# schematic_easyeda.net
KiCad netlist of a schematic drawn in EasyEDA
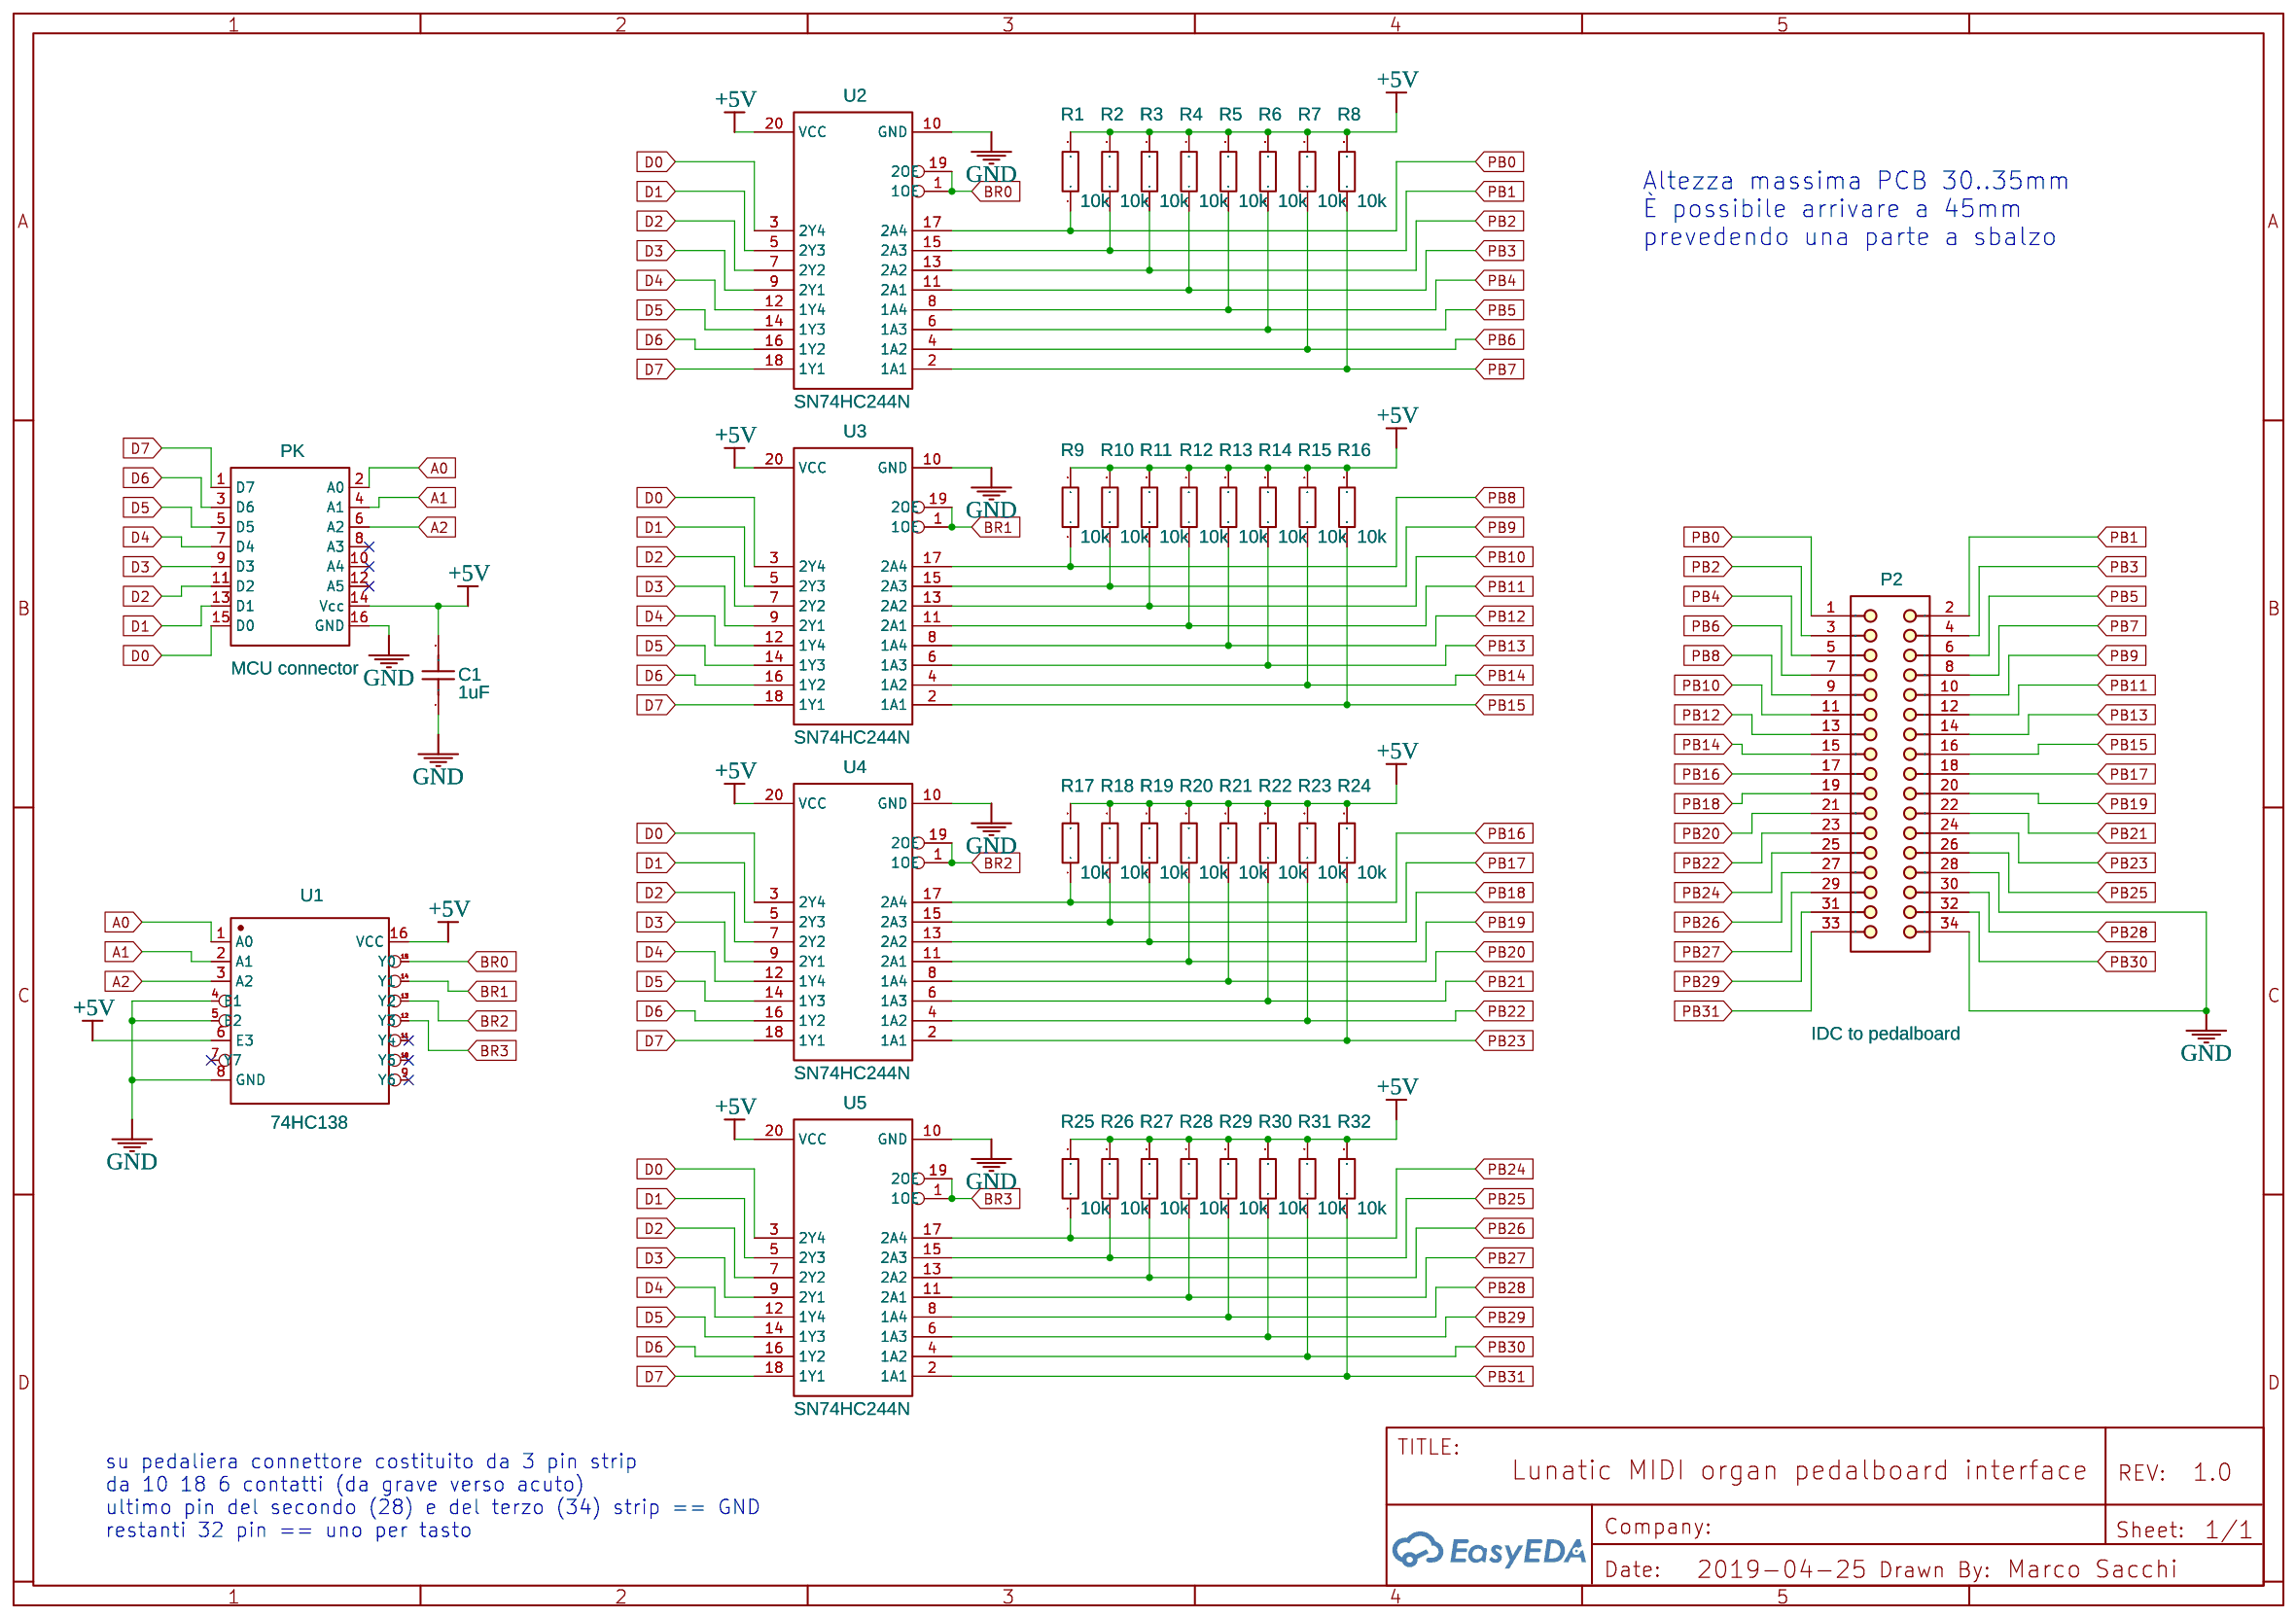
[diagram p0: schematic sheet]

(export (version "E")
  (design (tool "Eeschema 10.0.6"))
  (components
    (comp (ref "C1")
      (value "1uF")
      (fields (field (name "BOM_Manufacturer Part") "?"))
      (libsource (lib "") (part "Cap_RAD-0.1_US"))
    )
    (comp (ref "P2")
      (value "IDC to pedalboard")
      (fields
        (field (name "BOM_Manufacturer Part") "AWHW 34G-0202-T")
        (field (name "BOM_Supplier Part") "674-1243")
      )
      (libsource (lib "") (part "Unknown_950_385"))
    )
    (comp (ref "PK")
      (value "MCU connector")
      (fields (field (name "BOM_Manufacturer Part") "GEM"))
      (libsource (lib "") (part "Unknown_130_270"))
    )
    (comp (ref "R1")
      (value "10k")
      (fields (field (name "BOM_Manufacturer Part") "?"))
      (libsource (lib "") (part "Res_AXIAL-0.3(1/8W)_EU"))
    )
    (comp (ref "R2")
      (value "10k")
      (fields (field (name "BOM_Manufacturer Part") "?"))
      (libsource (lib "") (part "Res_AXIAL-0.3(1/8W)_EU"))
    )
    (comp (ref "R3")
      (value "10k")
      (fields (field (name "BOM_Manufacturer Part") "?"))
      (libsource (lib "") (part "Res_AXIAL-0.3(1/8W)_EU"))
    )
    (comp (ref "R4")
      (value "10k")
      (fields (field (name "BOM_Manufacturer Part") "?"))
      (libsource (lib "") (part "Res_AXIAL-0.3(1/8W)_EU"))
    )
    (comp (ref "R5")
      (value "10k")
      (fields (field (name "BOM_Manufacturer Part") "?"))
      (libsource (lib "") (part "Res_AXIAL-0.3(1/8W)_EU"))
    )
    (comp (ref "R6")
      (value "10k")
      (fields (field (name "BOM_Manufacturer Part") "?"))
      (libsource (lib "") (part "Res_AXIAL-0.3(1/8W)_EU"))
    )
    (comp (ref "R7")
      (value "10k")
      (fields (field (name "BOM_Manufacturer Part") "?"))
      (libsource (lib "") (part "Res_AXIAL-0.3(1/8W)_EU"))
    )
    (comp (ref "R8")
      (value "10k")
      (fields (field (name "BOM_Manufacturer Part") "?"))
      (libsource (lib "") (part "Res_AXIAL-0.3(1/8W)_EU"))
    )
    (comp (ref "R9")
      (value "10k")
      (fields (field (name "BOM_Manufacturer Part") "?"))
      (libsource (lib "") (part "Res_AXIAL-0.3(1/8W)_EU"))
    )
    (comp (ref "R10")
      (value "10k")
      (fields (field (name "BOM_Manufacturer Part") "?"))
      (libsource (lib "") (part "Res_AXIAL-0.3(1/8W)_EU"))
    )
    (comp (ref "R11")
      (value "10k")
      (fields (field (name "BOM_Manufacturer Part") "?"))
      (libsource (lib "") (part "Res_AXIAL-0.3(1/8W)_EU"))
    )
    (comp (ref "R12")
      (value "10k")
      (fields (field (name "BOM_Manufacturer Part") "?"))
      (libsource (lib "") (part "Res_AXIAL-0.3(1/8W)_EU"))
    )
    (comp (ref "R13")
      (value "10k")
      (fields (field (name "BOM_Manufacturer Part") "?"))
      (libsource (lib "") (part "Res_AXIAL-0.3(1/8W)_EU"))
    )
    (comp (ref "R14")
      (value "10k")
      (fields (field (name "BOM_Manufacturer Part") "?"))
      (libsource (lib "") (part "Res_AXIAL-0.3(1/8W)_EU"))
    )
    (comp (ref "R15")
      (value "10k")
      (fields (field (name "BOM_Manufacturer Part") "?"))
      (libsource (lib "") (part "Res_AXIAL-0.3(1/8W)_EU"))
    )
    (comp (ref "R16")
      (value "10k")
      (fields (field (name "BOM_Manufacturer Part") "?"))
      (libsource (lib "") (part "Res_AXIAL-0.3(1/8W)_EU"))
    )
    (comp (ref "R17")
      (value "10k")
      (fields (field (name "BOM_Manufacturer Part") "?"))
      (libsource (lib "") (part "Res_AXIAL-0.3(1/8W)_EU"))
    )
    (comp (ref "R18")
      (value "10k")
      (fields (field (name "BOM_Manufacturer Part") "?"))
      (libsource (lib "") (part "Res_AXIAL-0.3(1/8W)_EU"))
    )
    (comp (ref "R19")
      (value "10k")
      (fields (field (name "BOM_Manufacturer Part") "?"))
      (libsource (lib "") (part "Res_AXIAL-0.3(1/8W)_EU"))
    )
    (comp (ref "R20")
      (value "10k")
      (fields (field (name "BOM_Manufacturer Part") "?"))
      (libsource (lib "") (part "Res_AXIAL-0.3(1/8W)_EU"))
    )
    (comp (ref "R21")
      (value "10k")
      (fields (field (name "BOM_Manufacturer Part") "?"))
      (libsource (lib "") (part "Res_AXIAL-0.3(1/8W)_EU"))
    )
    (comp (ref "R22")
      (value "10k")
      (fields (field (name "BOM_Manufacturer Part") "?"))
      (libsource (lib "") (part "Res_AXIAL-0.3(1/8W)_EU"))
    )
    (comp (ref "R23")
      (value "10k")
      (fields (field (name "BOM_Manufacturer Part") "?"))
      (libsource (lib "") (part "Res_AXIAL-0.3(1/8W)_EU"))
    )
    (comp (ref "R24")
      (value "10k")
      (fields (field (name "BOM_Manufacturer Part") "?"))
      (libsource (lib "") (part "Res_AXIAL-0.3(1/8W)_EU"))
    )
    (comp (ref "R25")
      (value "10k")
      (fields (field (name "BOM_Manufacturer Part") "?"))
      (libsource (lib "") (part "Res_AXIAL-0.3(1/8W)_EU"))
    )
    (comp (ref "R26")
      (value "10k")
      (fields (field (name "BOM_Manufacturer Part") "?"))
      (libsource (lib "") (part "Res_AXIAL-0.3(1/8W)_EU"))
    )
    (comp (ref "R27")
      (value "10k")
      (fields (field (name "BOM_Manufacturer Part") "?"))
      (libsource (lib "") (part "Res_AXIAL-0.3(1/8W)_EU"))
    )
    (comp (ref "R28")
      (value "10k")
      (fields (field (name "BOM_Manufacturer Part") "?"))
      (libsource (lib "") (part "Res_AXIAL-0.3(1/8W)_EU"))
    )
    (comp (ref "R29")
      (value "10k")
      (fields (field (name "BOM_Manufacturer Part") "?"))
      (libsource (lib "") (part "Res_AXIAL-0.3(1/8W)_EU"))
    )
    (comp (ref "R30")
      (value "10k")
      (fields (field (name "BOM_Manufacturer Part") "?"))
      (libsource (lib "") (part "Res_AXIAL-0.3(1/8W)_EU"))
    )
    (comp (ref "R31")
      (value "10k")
      (fields (field (name "BOM_Manufacturer Part") "?"))
      (libsource (lib "") (part "Res_AXIAL-0.3(1/8W)_EU"))
    )
    (comp (ref "R32")
      (value "10k")
      (fields (field (name "BOM_Manufacturer Part") "?"))
      (libsource (lib "") (part "Res_AXIAL-0.3(1/8W)_EU"))
    )
    (comp (ref "U1")
      (value "74HC138")
      (fields (field (name "BOM_Supplier Part") "C5194"))
      (libsource (lib "") (part "Unknown_150_505"))
    )
    (comp (ref "U2")
      (value "SN74HC244N")
      (fields (field (name "BOM_Supplier Part") "333-3072"))
      (libsource (lib "") (part "Unknown_425_120"))
    )
    (comp (ref "U3")
      (value "SN74HC244N")
      (fields (field (name "BOM_Supplier Part") "333-3072"))
      (libsource (lib "") (part "Unknown_425_290"))
    )
    (comp (ref "U4")
      (value "SN74HC244N")
      (fields (field (name "BOM_Supplier Part") "333-3072"))
      (libsource (lib "") (part "Unknown_425_460"))
    )
    (comp (ref "U5")
      (value "SN74HC244N")
      (fields (field (name "BOM_Supplier Part") "333-3072"))
      (libsource (lib "") (part "Unknown_425_630"))
    )
  )
  (nets
    (net (code "1") (name "+5V") (class "Default")
      (node (ref "C1") (pin "2") (pinfunction "2_2") (pintype "unspecified"))
      (node (ref "PK") (pin "14") (pinfunction "Vcc_14") (pintype "passive"))
      (node (ref "R1") (pin "2") (pinfunction "2_2") (pintype "unspecified"))
      (node (ref "R10") (pin "2") (pinfunction "2_2") (pintype "unspecified"))
      (node (ref "R11") (pin "2") (pinfunction "2_2") (pintype "unspecified"))
      (node (ref "R12") (pin "2") (pinfunction "2_2") (pintype "unspecified"))
      (node (ref "R13") (pin "2") (pinfunction "2_2") (pintype "unspecified"))
      (node (ref "R14") (pin "2") (pinfunction "2_2") (pintype "unspecified"))
      (node (ref "R15") (pin "2") (pinfunction "2_2") (pintype "unspecified"))
      (node (ref "R16") (pin "2") (pinfunction "2_2") (pintype "unspecified"))
      (node (ref "R17") (pin "2") (pinfunction "2_2") (pintype "unspecified"))
      (node (ref "R18") (pin "2") (pinfunction "2_2") (pintype "unspecified"))
      (node (ref "R19") (pin "2") (pinfunction "2_2") (pintype "unspecified"))
      (node (ref "R2") (pin "2") (pinfunction "2_2") (pintype "unspecified"))
      (node (ref "R20") (pin "2") (pinfunction "2_2") (pintype "unspecified"))
      (node (ref "R21") (pin "2") (pinfunction "2_2") (pintype "unspecified"))
      (node (ref "R22") (pin "2") (pinfunction "2_2") (pintype "unspecified"))
      (node (ref "R23") (pin "2") (pinfunction "2_2") (pintype "unspecified"))
      (node (ref "R24") (pin "2") (pinfunction "2_2") (pintype "unspecified"))
      (node (ref "R25") (pin "2") (pinfunction "2_2") (pintype "unspecified"))
      (node (ref "R26") (pin "2") (pinfunction "2_2") (pintype "unspecified"))
      (node (ref "R27") (pin "2") (pinfunction "2_2") (pintype "unspecified"))
      (node (ref "R28") (pin "2") (pinfunction "2_2") (pintype "unspecified"))
      (node (ref "R29") (pin "2") (pinfunction "2_2") (pintype "unspecified"))
      (node (ref "R3") (pin "2") (pinfunction "2_2") (pintype "unspecified"))
      (node (ref "R30") (pin "2") (pinfunction "2_2") (pintype "unspecified"))
      (node (ref "R31") (pin "2") (pinfunction "2_2") (pintype "unspecified"))
      (node (ref "R32") (pin "2") (pinfunction "2_2") (pintype "unspecified"))
      (node (ref "R4") (pin "2") (pinfunction "2_2") (pintype "unspecified"))
      (node (ref "R5") (pin "2") (pinfunction "2_2") (pintype "unspecified"))
      (node (ref "R6") (pin "2") (pinfunction "2_2") (pintype "unspecified"))
      (node (ref "R7") (pin "2") (pinfunction "2_2") (pintype "unspecified"))
      (node (ref "R8") (pin "2") (pinfunction "2_2") (pintype "unspecified"))
      (node (ref "R9") (pin "2") (pinfunction "2_2") (pintype "unspecified"))
      (node (ref "U1") (pin "16") (pinfunction "VCC_16") (pintype "unspecified"))
      (node (ref "U1") (pin "6") (pinfunction "E3_6") (pintype "unspecified"))
      (node (ref "U2") (pin "20") (pinfunction "VCC_20") (pintype "passive"))
      (node (ref "U3") (pin "20") (pinfunction "VCC_20") (pintype "passive"))
      (node (ref "U4") (pin "20") (pinfunction "VCC_20") (pintype "passive"))
      (node (ref "U5") (pin "20") (pinfunction "VCC_20") (pintype "passive"))
    )
    (net (code "2") (name "A0") (class "Default")
      (node (ref "PK") (pin "2") (pinfunction "A0_2") (pintype "output"))
      (node (ref "U1") (pin "1") (pinfunction "A0_1") (pintype "unspecified"))
    )
    (net (code "3") (name "A1") (class "Default")
      (node (ref "PK") (pin "4") (pinfunction "A1_4") (pintype "output"))
      (node (ref "U1") (pin "2") (pinfunction "A1_2") (pintype "unspecified"))
    )
    (net (code "4") (name "A2") (class "Default")
      (node (ref "PK") (pin "6") (pinfunction "A2_6") (pintype "output"))
      (node (ref "U1") (pin "3") (pinfunction "A2_3") (pintype "unspecified"))
    )
    (net (code "5") (name "BR0") (class "Default")
      (node (ref "U1") (pin "15") (pinfunction "Y0_15") (pintype "unspecified"))
      (node (ref "U2") (pin "1") (pinfunction "1OE_1") (pintype "input"))
      (node (ref "U2") (pin "19") (pinfunction "2OE_19") (pintype "input"))
    )
    (net (code "6") (name "BR1") (class "Default")
      (node (ref "U1") (pin "14") (pinfunction "Y1_14") (pintype "unspecified"))
      (node (ref "U3") (pin "1") (pinfunction "1OE_1") (pintype "input"))
      (node (ref "U3") (pin "19") (pinfunction "2OE_19") (pintype "input"))
    )
    (net (code "7") (name "BR2") (class "Default")
      (node (ref "U1") (pin "13") (pinfunction "Y2_13") (pintype "unspecified"))
      (node (ref "U4") (pin "1") (pinfunction "1OE_1") (pintype "input"))
      (node (ref "U4") (pin "19") (pinfunction "2OE_19") (pintype "input"))
    )
    (net (code "8") (name "BR3") (class "Default")
      (node (ref "U1") (pin "12") (pinfunction "Y3_12") (pintype "unspecified"))
      (node (ref "U5") (pin "1") (pinfunction "1OE_1") (pintype "input"))
      (node (ref "U5") (pin "19") (pinfunction "2OE_19") (pintype "input"))
    )
    (net (code "9") (name "D0") (class "Default")
      (node (ref "PK") (pin "15") (pinfunction "D0_15") (pintype "bidirectional"))
      (node (ref "U2") (pin "3") (pinfunction "2Y4_3") (pintype "output"))
      (node (ref "U3") (pin "3") (pinfunction "2Y4_3") (pintype "output"))
      (node (ref "U4") (pin "3") (pinfunction "2Y4_3") (pintype "output"))
      (node (ref "U5") (pin "3") (pinfunction "2Y4_3") (pintype "output"))
    )
    (net (code "10") (name "D1") (class "Default")
      (node (ref "PK") (pin "13") (pinfunction "D1_13") (pintype "bidirectional"))
      (node (ref "U2") (pin "5") (pinfunction "2Y3_5") (pintype "output"))
      (node (ref "U3") (pin "5") (pinfunction "2Y3_5") (pintype "output"))
      (node (ref "U4") (pin "5") (pinfunction "2Y3_5") (pintype "output"))
      (node (ref "U5") (pin "5") (pinfunction "2Y3_5") (pintype "output"))
    )
    (net (code "11") (name "D2") (class "Default")
      (node (ref "PK") (pin "11") (pinfunction "D2_11") (pintype "bidirectional"))
      (node (ref "U2") (pin "7") (pinfunction "2Y2_7") (pintype "output"))
      (node (ref "U3") (pin "7") (pinfunction "2Y2_7") (pintype "output"))
      (node (ref "U4") (pin "7") (pinfunction "2Y2_7") (pintype "output"))
      (node (ref "U5") (pin "7") (pinfunction "2Y2_7") (pintype "output"))
    )
    (net (code "12") (name "D3") (class "Default")
      (node (ref "PK") (pin "9") (pinfunction "D3_9") (pintype "bidirectional"))
      (node (ref "U2") (pin "9") (pinfunction "2Y1_9") (pintype "output"))
      (node (ref "U3") (pin "9") (pinfunction "2Y1_9") (pintype "output"))
      (node (ref "U4") (pin "9") (pinfunction "2Y1_9") (pintype "output"))
      (node (ref "U5") (pin "9") (pinfunction "2Y1_9") (pintype "output"))
    )
    (net (code "13") (name "D4") (class "Default")
      (node (ref "PK") (pin "7") (pinfunction "D4_7") (pintype "bidirectional"))
      (node (ref "U2") (pin "12") (pinfunction "1Y4_12") (pintype "output"))
      (node (ref "U3") (pin "12") (pinfunction "1Y4_12") (pintype "output"))
      (node (ref "U4") (pin "12") (pinfunction "1Y4_12") (pintype "output"))
      (node (ref "U5") (pin "12") (pinfunction "1Y4_12") (pintype "output"))
    )
    (net (code "14") (name "D5") (class "Default")
      (node (ref "PK") (pin "5") (pinfunction "D5_5") (pintype "bidirectional"))
      (node (ref "U2") (pin "14") (pinfunction "1Y3_14") (pintype "output"))
      (node (ref "U3") (pin "14") (pinfunction "1Y3_14") (pintype "output"))
      (node (ref "U4") (pin "14") (pinfunction "1Y3_14") (pintype "output"))
      (node (ref "U5") (pin "14") (pinfunction "1Y3_14") (pintype "output"))
    )
    (net (code "15") (name "D6") (class "Default")
      (node (ref "PK") (pin "3") (pinfunction "D6_3") (pintype "bidirectional"))
      (node (ref "U2") (pin "16") (pinfunction "1Y2_16") (pintype "output"))
      (node (ref "U3") (pin "16") (pinfunction "1Y2_16") (pintype "output"))
      (node (ref "U4") (pin "16") (pinfunction "1Y2_16") (pintype "output"))
      (node (ref "U5") (pin "16") (pinfunction "1Y2_16") (pintype "output"))
    )
    (net (code "16") (name "D7") (class "Default")
      (node (ref "PK") (pin "1") (pinfunction "D7_1") (pintype "bidirectional"))
      (node (ref "U2") (pin "18") (pinfunction "1Y1_18") (pintype "output"))
      (node (ref "U3") (pin "18") (pinfunction "1Y1_18") (pintype "output"))
      (node (ref "U4") (pin "18") (pinfunction "1Y1_18") (pintype "output"))
      (node (ref "U5") (pin "18") (pinfunction "1Y1_18") (pintype "output"))
    )
    (net (code "17") (name "GND") (class "Default")
      (node (ref "C1") (pin "1") (pinfunction "1_1") (pintype "unspecified"))
      (node (ref "P2") (pin "28") (pinfunction "28_28") (pintype "unspecified"))
      (node (ref "P2") (pin "34") (pinfunction "34_34") (pintype "unspecified"))
      (node (ref "PK") (pin "16") (pinfunction "GND_16") (pintype "passive"))
      (node (ref "U1") (pin "4") (pinfunction "E1_4") (pintype "unspecified"))
      (node (ref "U1") (pin "5") (pinfunction "E2_5") (pintype "unspecified"))
      (node (ref "U1") (pin "8") (pinfunction "GND_8") (pintype "unspecified"))
      (node (ref "U2") (pin "10") (pinfunction "GND_10") (pintype "unspecified"))
      (node (ref "U3") (pin "10") (pinfunction "GND_10") (pintype "unspecified"))
      (node (ref "U4") (pin "10") (pinfunction "GND_10") (pintype "unspecified"))
      (node (ref "U5") (pin "10") (pinfunction "GND_10") (pintype "unspecified"))
    )
    (net (code "18") (name "PB0") (class "Default")
      (node (ref "P2") (pin "1") (pinfunction "1_1") (pintype "unspecified"))
      (node (ref "R1") (pin "1") (pinfunction "1_1") (pintype "unspecified"))
      (node (ref "U2") (pin "17") (pinfunction "2A4_17") (pintype "input"))
    )
    (net (code "19") (name "PB1") (class "Default")
      (node (ref "P2") (pin "2") (pinfunction "2_2") (pintype "unspecified"))
      (node (ref "R2") (pin "1") (pinfunction "1_1") (pintype "unspecified"))
      (node (ref "U2") (pin "15") (pinfunction "2A3_15") (pintype "input"))
    )
    (net (code "20") (name "PB2") (class "Default")
      (node (ref "P2") (pin "3") (pinfunction "3_3") (pintype "unspecified"))
      (node (ref "R3") (pin "1") (pinfunction "1_1") (pintype "unspecified"))
      (node (ref "U2") (pin "13") (pinfunction "2A2_13") (pintype "input"))
    )
    (net (code "21") (name "PB3") (class "Default")
      (node (ref "P2") (pin "4") (pinfunction "4_4") (pintype "unspecified"))
      (node (ref "R4") (pin "1") (pinfunction "1_1") (pintype "unspecified"))
      (node (ref "U2") (pin "11") (pinfunction "2A1_11") (pintype "input"))
    )
    (net (code "22") (name "PB4") (class "Default")
      (node (ref "P2") (pin "5") (pinfunction "5_5") (pintype "unspecified"))
      (node (ref "R5") (pin "1") (pinfunction "1_1") (pintype "unspecified"))
      (node (ref "U2") (pin "8") (pinfunction "1A4_8") (pintype "input"))
    )
    (net (code "23") (name "PB5") (class "Default")
      (node (ref "P2") (pin "6") (pinfunction "6_6") (pintype "unspecified"))
      (node (ref "R6") (pin "1") (pinfunction "1_1") (pintype "unspecified"))
      (node (ref "U2") (pin "6") (pinfunction "1A3_6") (pintype "input"))
    )
    (net (code "24") (name "PB6") (class "Default")
      (node (ref "P2") (pin "7") (pinfunction "7_7") (pintype "unspecified"))
      (node (ref "R7") (pin "1") (pinfunction "1_1") (pintype "unspecified"))
      (node (ref "U2") (pin "4") (pinfunction "1A2_4") (pintype "input"))
    )
    (net (code "25") (name "PB7") (class "Default")
      (node (ref "P2") (pin "8") (pinfunction "8_8") (pintype "unspecified"))
      (node (ref "R8") (pin "1") (pinfunction "1_1") (pintype "unspecified"))
      (node (ref "U2") (pin "2") (pinfunction "1A1_2") (pintype "input"))
    )
    (net (code "26") (name "PB8") (class "Default")
      (node (ref "P2") (pin "9") (pinfunction "9_9") (pintype "unspecified"))
      (node (ref "R9") (pin "1") (pinfunction "1_1") (pintype "unspecified"))
      (node (ref "U3") (pin "17") (pinfunction "2A4_17") (pintype "input"))
    )
    (net (code "27") (name "PB9") (class "Default")
      (node (ref "P2") (pin "10") (pinfunction "10_10") (pintype "unspecified"))
      (node (ref "R10") (pin "1") (pinfunction "1_1") (pintype "unspecified"))
      (node (ref "U3") (pin "15") (pinfunction "2A3_15") (pintype "input"))
    )
    (net (code "28") (name "PB10") (class "Default")
      (node (ref "P2") (pin "11") (pinfunction "11_11") (pintype "unspecified"))
      (node (ref "R11") (pin "1") (pinfunction "1_1") (pintype "unspecified"))
      (node (ref "U3") (pin "13") (pinfunction "2A2_13") (pintype "input"))
    )
    (net (code "29") (name "PB11") (class "Default")
      (node (ref "P2") (pin "12") (pinfunction "12_12") (pintype "unspecified"))
      (node (ref "R12") (pin "1") (pinfunction "1_1") (pintype "unspecified"))
      (node (ref "U3") (pin "11") (pinfunction "2A1_11") (pintype "input"))
    )
    (net (code "30") (name "PB12") (class "Default")
      (node (ref "P2") (pin "13") (pinfunction "13_13") (pintype "unspecified"))
      (node (ref "R13") (pin "1") (pinfunction "1_1") (pintype "unspecified"))
      (node (ref "U3") (pin "8") (pinfunction "1A4_8") (pintype "input"))
    )
    (net (code "31") (name "PB13") (class "Default")
      (node (ref "P2") (pin "14") (pinfunction "14_14") (pintype "unspecified"))
      (node (ref "R14") (pin "1") (pinfunction "1_1") (pintype "unspecified"))
      (node (ref "U3") (pin "6") (pinfunction "1A3_6") (pintype "input"))
    )
    (net (code "32") (name "PB14") (class "Default")
      (node (ref "P2") (pin "15") (pinfunction "15_15") (pintype "unspecified"))
      (node (ref "R15") (pin "1") (pinfunction "1_1") (pintype "unspecified"))
      (node (ref "U3") (pin "4") (pinfunction "1A2_4") (pintype "input"))
    )
    (net (code "33") (name "PB15") (class "Default")
      (node (ref "P2") (pin "16") (pinfunction "16_16") (pintype "unspecified"))
      (node (ref "R16") (pin "1") (pinfunction "1_1") (pintype "unspecified"))
      (node (ref "U3") (pin "2") (pinfunction "1A1_2") (pintype "input"))
    )
    (net (code "34") (name "PB16") (class "Default")
      (node (ref "P2") (pin "17") (pinfunction "17_17") (pintype "unspecified"))
      (node (ref "R17") (pin "1") (pinfunction "1_1") (pintype "unspecified"))
      (node (ref "U4") (pin "17") (pinfunction "2A4_17") (pintype "input"))
    )
    (net (code "35") (name "PB17") (class "Default")
      (node (ref "P2") (pin "18") (pinfunction "18_18") (pintype "unspecified"))
      (node (ref "R18") (pin "1") (pinfunction "1_1") (pintype "unspecified"))
      (node (ref "U4") (pin "15") (pinfunction "2A3_15") (pintype "input"))
    )
    (net (code "36") (name "PB18") (class "Default")
      (node (ref "P2") (pin "19") (pinfunction "19_19") (pintype "unspecified"))
      (node (ref "R19") (pin "1") (pinfunction "1_1") (pintype "unspecified"))
      (node (ref "U4") (pin "13") (pinfunction "2A2_13") (pintype "input"))
    )
    (net (code "37") (name "PB19") (class "Default")
      (node (ref "P2") (pin "20") (pinfunction "20_20") (pintype "unspecified"))
      (node (ref "R20") (pin "1") (pinfunction "1_1") (pintype "unspecified"))
      (node (ref "U4") (pin "11") (pinfunction "2A1_11") (pintype "input"))
    )
    (net (code "38") (name "PB20") (class "Default")
      (node (ref "P2") (pin "21") (pinfunction "21_21") (pintype "unspecified"))
      (node (ref "R21") (pin "1") (pinfunction "1_1") (pintype "unspecified"))
      (node (ref "U4") (pin "8") (pinfunction "1A4_8") (pintype "input"))
    )
    (net (code "39") (name "PB21") (class "Default")
      (node (ref "P2") (pin "22") (pinfunction "22_22") (pintype "unspecified"))
      (node (ref "R22") (pin "1") (pinfunction "1_1") (pintype "unspecified"))
      (node (ref "U4") (pin "6") (pinfunction "1A3_6") (pintype "input"))
    )
    (net (code "40") (name "PB22") (class "Default")
      (node (ref "P2") (pin "23") (pinfunction "23_23") (pintype "unspecified"))
      (node (ref "R23") (pin "1") (pinfunction "1_1") (pintype "unspecified"))
      (node (ref "U4") (pin "4") (pinfunction "1A2_4") (pintype "input"))
    )
    (net (code "41") (name "PB23") (class "Default")
      (node (ref "P2") (pin "24") (pinfunction "24_24") (pintype "unspecified"))
      (node (ref "R24") (pin "1") (pinfunction "1_1") (pintype "unspecified"))
      (node (ref "U4") (pin "2") (pinfunction "1A1_2") (pintype "input"))
    )
    (net (code "42") (name "PB24") (class "Default")
      (node (ref "P2") (pin "25") (pinfunction "25_25") (pintype "unspecified"))
      (node (ref "R25") (pin "1") (pinfunction "1_1") (pintype "unspecified"))
      (node (ref "U5") (pin "17") (pinfunction "2A4_17") (pintype "input"))
    )
    (net (code "43") (name "PB25") (class "Default")
      (node (ref "P2") (pin "26") (pinfunction "26_26") (pintype "unspecified"))
      (node (ref "R26") (pin "1") (pinfunction "1_1") (pintype "unspecified"))
      (node (ref "U5") (pin "15") (pinfunction "2A3_15") (pintype "input"))
    )
    (net (code "44") (name "PB26") (class "Default")
      (node (ref "P2") (pin "27") (pinfunction "27_27") (pintype "unspecified"))
      (node (ref "R27") (pin "1") (pinfunction "1_1") (pintype "unspecified"))
      (node (ref "U5") (pin "13") (pinfunction "2A2_13") (pintype "input"))
    )
    (net (code "45") (name "PB27") (class "Default")
      (node (ref "P2") (pin "29") (pinfunction "29_29") (pintype "unspecified"))
      (node (ref "R28") (pin "1") (pinfunction "1_1") (pintype "unspecified"))
      (node (ref "U5") (pin "11") (pinfunction "2A1_11") (pintype "input"))
    )
    (net (code "46") (name "PB28") (class "Default")
      (node (ref "P2") (pin "30") (pinfunction "30_30") (pintype "unspecified"))
      (node (ref "R29") (pin "1") (pinfunction "1_1") (pintype "unspecified"))
      (node (ref "U5") (pin "8") (pinfunction "1A4_8") (pintype "input"))
    )
    (net (code "47") (name "PB29") (class "Default")
      (node (ref "P2") (pin "31") (pinfunction "31_31") (pintype "unspecified"))
      (node (ref "R30") (pin "1") (pinfunction "1_1") (pintype "unspecified"))
      (node (ref "U5") (pin "6") (pinfunction "1A3_6") (pintype "input"))
    )
    (net (code "48") (name "PB30") (class "Default")
      (node (ref "P2") (pin "32") (pinfunction "32_32") (pintype "unspecified"))
      (node (ref "R31") (pin "1") (pinfunction "1_1") (pintype "unspecified"))
      (node (ref "U5") (pin "4") (pinfunction "1A2_4") (pintype "input"))
    )
    (net (code "49") (name "PB31") (class "Default")
      (node (ref "P2") (pin "33") (pinfunction "33_33") (pintype "unspecified"))
      (node (ref "R32") (pin "1") (pinfunction "1_1") (pintype "unspecified"))
      (node (ref "U5") (pin "2") (pinfunction "1A1_2") (pintype "input"))
    )
    (net (code "50") (name "unconnected-(PK-A3-Pad8)") (class "Default")
      (node (ref "PK") (pin "8") (pinfunction "A3_8") (pintype "output+no_connect"))
    )
    (net (code "51") (name "unconnected-(PK-A4-Pad10)") (class "Default")
      (node (ref "PK") (pin "10") (pinfunction "A4_10") (pintype "output+no_connect"))
    )
    (net (code "52") (name "unconnected-(PK-A5-Pad12)") (class "Default")
      (node (ref "PK") (pin "12") (pinfunction "A5_12") (pintype "output+no_connect"))
    )
    (net (code "53") (name "unconnected-(U1-Y4-Pad11)") (class "Default")
      (node (ref "U1") (pin "11") (pinfunction "Y4_11") (pintype "unspecified+no_connect"))
    )
    (net (code "54") (name "unconnected-(U1-Y5-Pad10)") (class "Default")
      (node (ref "U1") (pin "10") (pinfunction "Y5_10") (pintype "unspecified+no_connect"))
    )
    (net (code "55") (name "unconnected-(U1-Y6-Pad9)") (class "Default")
      (node (ref "U1") (pin "9") (pinfunction "Y6_9") (pintype "unspecified+no_connect"))
    )
    (net (code "56") (name "unconnected-(U1-Y7-Pad7)") (class "Default")
      (node (ref "U1") (pin "7") (pinfunction "Y7_7") (pintype "unspecified+no_connect"))
    )
  )
)
